# Papilio-Audio_Wing.net
KiCad netlist of a schematic drawn in EAGLE
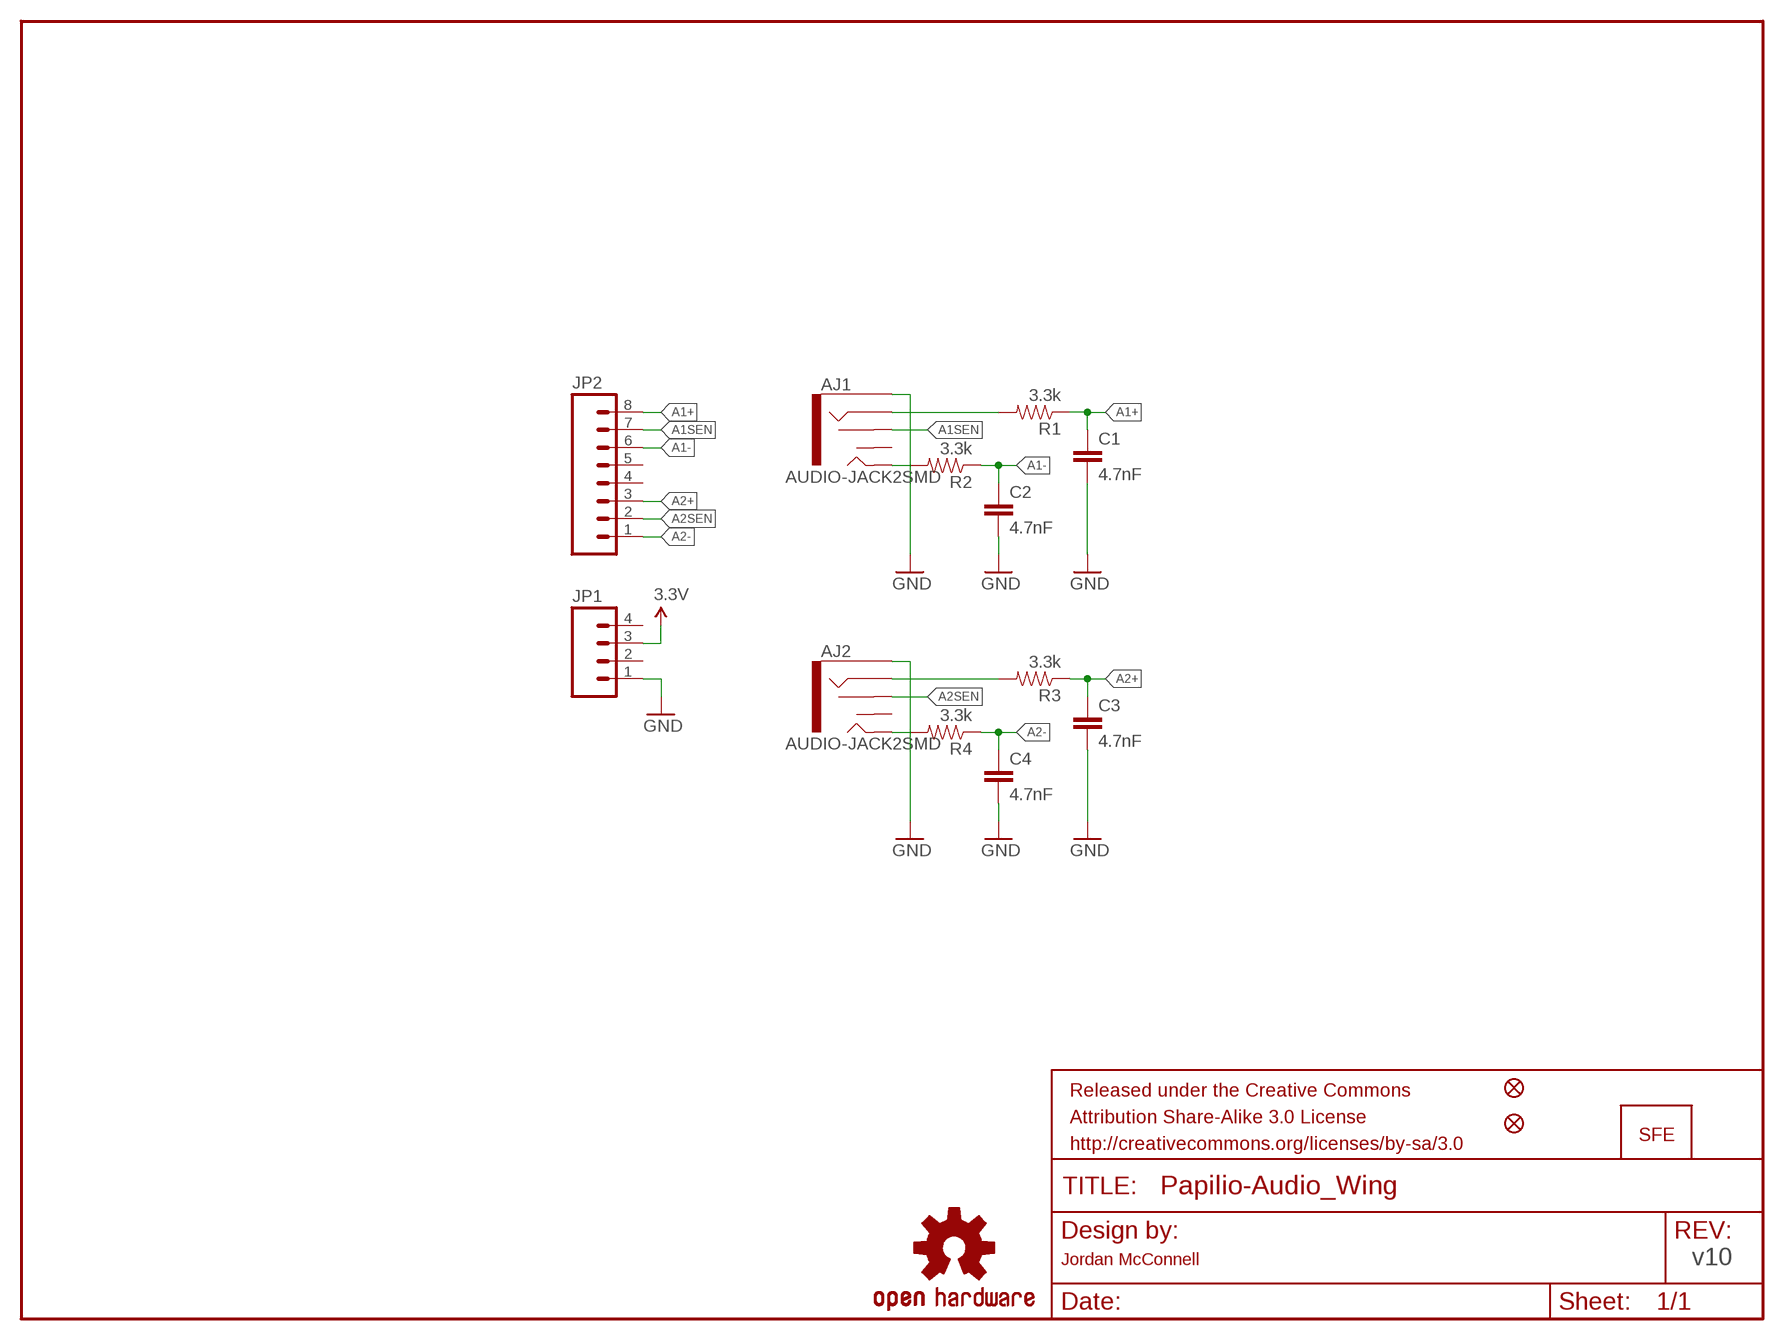
[diagram p0: schematic, sheet 1]

(export (version "E")
  (design (tool "Eeschema 10.0.6"))
  (components
    (comp (ref "AJ1")
      (value "AUDIO-JACK2SMD")
      (footprint "eagle-import:AUDIO-JACK-3.5MM-SMD")
      (libsource (lib "eagle-import") (part "AUDIO-JACK2SMD"))
    )
    (comp (ref "AJ2")
      (value "AUDIO-JACK2SMD")
      (footprint "eagle-import:AUDIO-JACK-3.5MM-SMD")
      (libsource (lib "eagle-import") (part "AUDIO-JACK2SMD"))
    )
    (comp (ref "C1")
      (value "4.7nF")
      (footprint "eagle-import:0402-CAP")
      (libsource (lib "eagle-import") (part "CAP0402-CAP"))
    )
    (comp (ref "C2")
      (value "4.7nF")
      (footprint "eagle-import:0402-CAP")
      (libsource (lib "eagle-import") (part "CAP0402-CAP"))
    )
    (comp (ref "C3")
      (value "4.7nF")
      (footprint "eagle-import:0402-CAP")
      (libsource (lib "eagle-import") (part "CAP0402-CAP"))
    )
    (comp (ref "C4")
      (value "4.7nF")
      (footprint "eagle-import:0402-CAP")
      (libsource (lib "eagle-import") (part "CAP0402-CAP"))
    )
    (comp (ref "FRAME2")
      (value "FRAME-LETTER")
      (footprint "eagle-import:CREATIVE_COMMONS")
      (libsource (lib "eagle-import") (part "FRAME-LETTER"))
    )
    (comp (ref "JP1")
      (value "M04PTH")
      (footprint "eagle-import:1X04")
      (libsource (lib "eagle-import") (part "M04PTH"))
    )
    (comp (ref "JP2")
      (value "M081X08")
      (footprint "eagle-import:1X08")
      (libsource (lib "eagle-import") (part "M081X08"))
    )
    (comp (ref "JP4")
      (value "LOGO-SFENEW")
      (footprint "eagle-import:SFE-NEW-WEBLOGO")
      (libsource (lib "eagle-import") (part "LOGO-SFENEW"))
    )
    (comp (ref "JP5")
      (value "FIDUCIALUFIDUCIAL")
      (footprint "eagle-import:MICRO-FIDUCIAL")
      (libsource (lib "eagle-import") (part "FIDUCIALUFIDUCIAL"))
    )
    (comp (ref "JP6")
      (value "FIDUCIALUFIDUCIAL")
      (footprint "eagle-import:MICRO-FIDUCIAL")
      (libsource (lib "eagle-import") (part "FIDUCIALUFIDUCIAL"))
    )
    (comp (ref "R1")
      (value "3.3k")
      (footprint "eagle-import:0402-RES")
      (libsource (lib "eagle-import") (part "RESISTOR0402-RES"))
    )
    (comp (ref "R2")
      (value "3.3k")
      (footprint "eagle-import:0402-RES")
      (libsource (lib "eagle-import") (part "RESISTOR0402-RES"))
    )
    (comp (ref "R3")
      (value "3.3k")
      (footprint "eagle-import:0402-RES")
      (libsource (lib "eagle-import") (part "RESISTOR0402-RES"))
    )
    (comp (ref "R4")
      (value "3.3k")
      (footprint "eagle-import:0402-RES")
      (libsource (lib "eagle-import") (part "RESISTOR0402-RES"))
    )
    (comp (ref "U$1")
      (value "OSHW-LOGOS")
      (footprint "eagle-import:OSHW-LOGO-S")
      (libsource (lib "eagle-import") (part "OSHW-LOGOS"))
    )
  )
  (nets
    (net (code "1") (name "3.3V") (class "Default")
      (node (ref "JP1") (pin "3") (pinfunction "3_3") (pintype "passive"))
    )
    (net (code "2") (name "A1+") (class "Default")
      (node (ref "C1") (pin "1") (pinfunction "1_1") (pintype "passive"))
      (node (ref "JP2") (pin "8") (pinfunction "8_8") (pintype "passive"))
      (node (ref "R1") (pin "1") (pinfunction "1_1") (pintype "passive"))
    )
    (net (code "3") (name "A1-") (class "Default")
      (node (ref "C2") (pin "1") (pinfunction "1_1") (pintype "passive"))
      (node (ref "JP2") (pin "6") (pinfunction "6_6") (pintype "passive"))
      (node (ref "R2") (pin "1") (pinfunction "1_1") (pintype "passive"))
    )
    (net (code "4") (name "A1SEN") (class "Default")
      (node (ref "AJ1") (pin "RSH") (pinfunction "RSH_RSH") (pintype "bidirectional"))
      (node (ref "JP2") (pin "7") (pinfunction "7_7") (pintype "passive"))
    )
    (net (code "5") (name "A2+") (class "Default")
      (node (ref "C3") (pin "1") (pinfunction "1_1") (pintype "passive"))
      (node (ref "JP2") (pin "3") (pinfunction "3_3") (pintype "passive"))
      (node (ref "R3") (pin "1") (pinfunction "1_1") (pintype "passive"))
    )
    (net (code "6") (name "A2-") (class "Default")
      (node (ref "C4") (pin "1") (pinfunction "1_1") (pintype "passive"))
      (node (ref "JP2") (pin "1") (pinfunction "1_1") (pintype "passive"))
      (node (ref "R4") (pin "1") (pinfunction "1_1") (pintype "passive"))
    )
    (net (code "7") (name "A2SEN") (class "Default")
      (node (ref "AJ2") (pin "RSH") (pinfunction "RSH_RSH") (pintype "bidirectional"))
      (node (ref "JP2") (pin "2") (pinfunction "2_2") (pintype "passive"))
    )
    (net (code "8") (name "GND") (class "Default")
      (node (ref "AJ1") (pin "SLEEVE") (pinfunction "SLEEVE_SLEEVE") (pintype "bidirectional"))
      (node (ref "AJ2") (pin "SLEEVE") (pinfunction "SLEEVE_SLEEVE") (pintype "bidirectional"))
      (node (ref "C1") (pin "2") (pinfunction "2_2") (pintype "passive"))
      (node (ref "C2") (pin "2") (pinfunction "2_2") (pintype "passive"))
      (node (ref "C3") (pin "2") (pinfunction "2_2") (pintype "passive"))
      (node (ref "C4") (pin "2") (pinfunction "2_2") (pintype "passive"))
      (node (ref "JP1") (pin "1") (pinfunction "1_1") (pintype "passive"))
    )
    (net (code "9") (name "Net-(AJ1-PadRING)") (class "Default")
      (node (ref "AJ1") (pin "RING") (pinfunction "RING_RING") (pintype "bidirectional"))
      (node (ref "R1") (pin "2") (pinfunction "2_2") (pintype "passive"))
    )
    (net (code "10") (name "Net-(AJ1-PadTIP)") (class "Default")
      (node (ref "AJ1") (pin "TIP") (pinfunction "TIP_TIP") (pintype "bidirectional"))
      (node (ref "R2") (pin "2") (pinfunction "2_2") (pintype "passive"))
    )
    (net (code "11") (name "Net-(AJ2-PadRING)") (class "Default")
      (node (ref "AJ2") (pin "RING") (pinfunction "RING_RING") (pintype "bidirectional"))
      (node (ref "R3") (pin "2") (pinfunction "2_2") (pintype "passive"))
    )
    (net (code "12") (name "Net-(AJ2-PadTIP)") (class "Default")
      (node (ref "AJ2") (pin "TIP") (pinfunction "TIP_TIP") (pintype "bidirectional"))
      (node (ref "R4") (pin "2") (pinfunction "2_2") (pintype "passive"))
    )
    (net (code "13") (name "unconnected-(AJ1-PadTSH)") (class "Default")
      (node (ref "AJ1") (pin "TSH") (pinfunction "TSH_TSH") (pintype "bidirectional"))
    )
    (net (code "14") (name "unconnected-(AJ2-PadTSH)") (class "Default")
      (node (ref "AJ2") (pin "TSH") (pinfunction "TSH_TSH") (pintype "bidirectional"))
    )
    (net (code "15") (name "unconnected-(JP1-Pad2)") (class "Default")
      (node (ref "JP1") (pin "2") (pinfunction "2_2") (pintype "passive"))
    )
    (net (code "16") (name "unconnected-(JP1-Pad4)") (class "Default")
      (node (ref "JP1") (pin "4") (pinfunction "4_4") (pintype "passive"))
    )
    (net (code "17") (name "unconnected-(JP2-Pad4)") (class "Default")
      (node (ref "JP2") (pin "4") (pinfunction "4_4") (pintype "passive"))
    )
    (net (code "18") (name "unconnected-(JP2-Pad5)") (class "Default")
      (node (ref "JP2") (pin "5") (pinfunction "5_5") (pintype "passive"))
    )
  )
)
